# LPC2148_Engine_Room.net
KiCad netlist of a schematic drawn in EAGLE
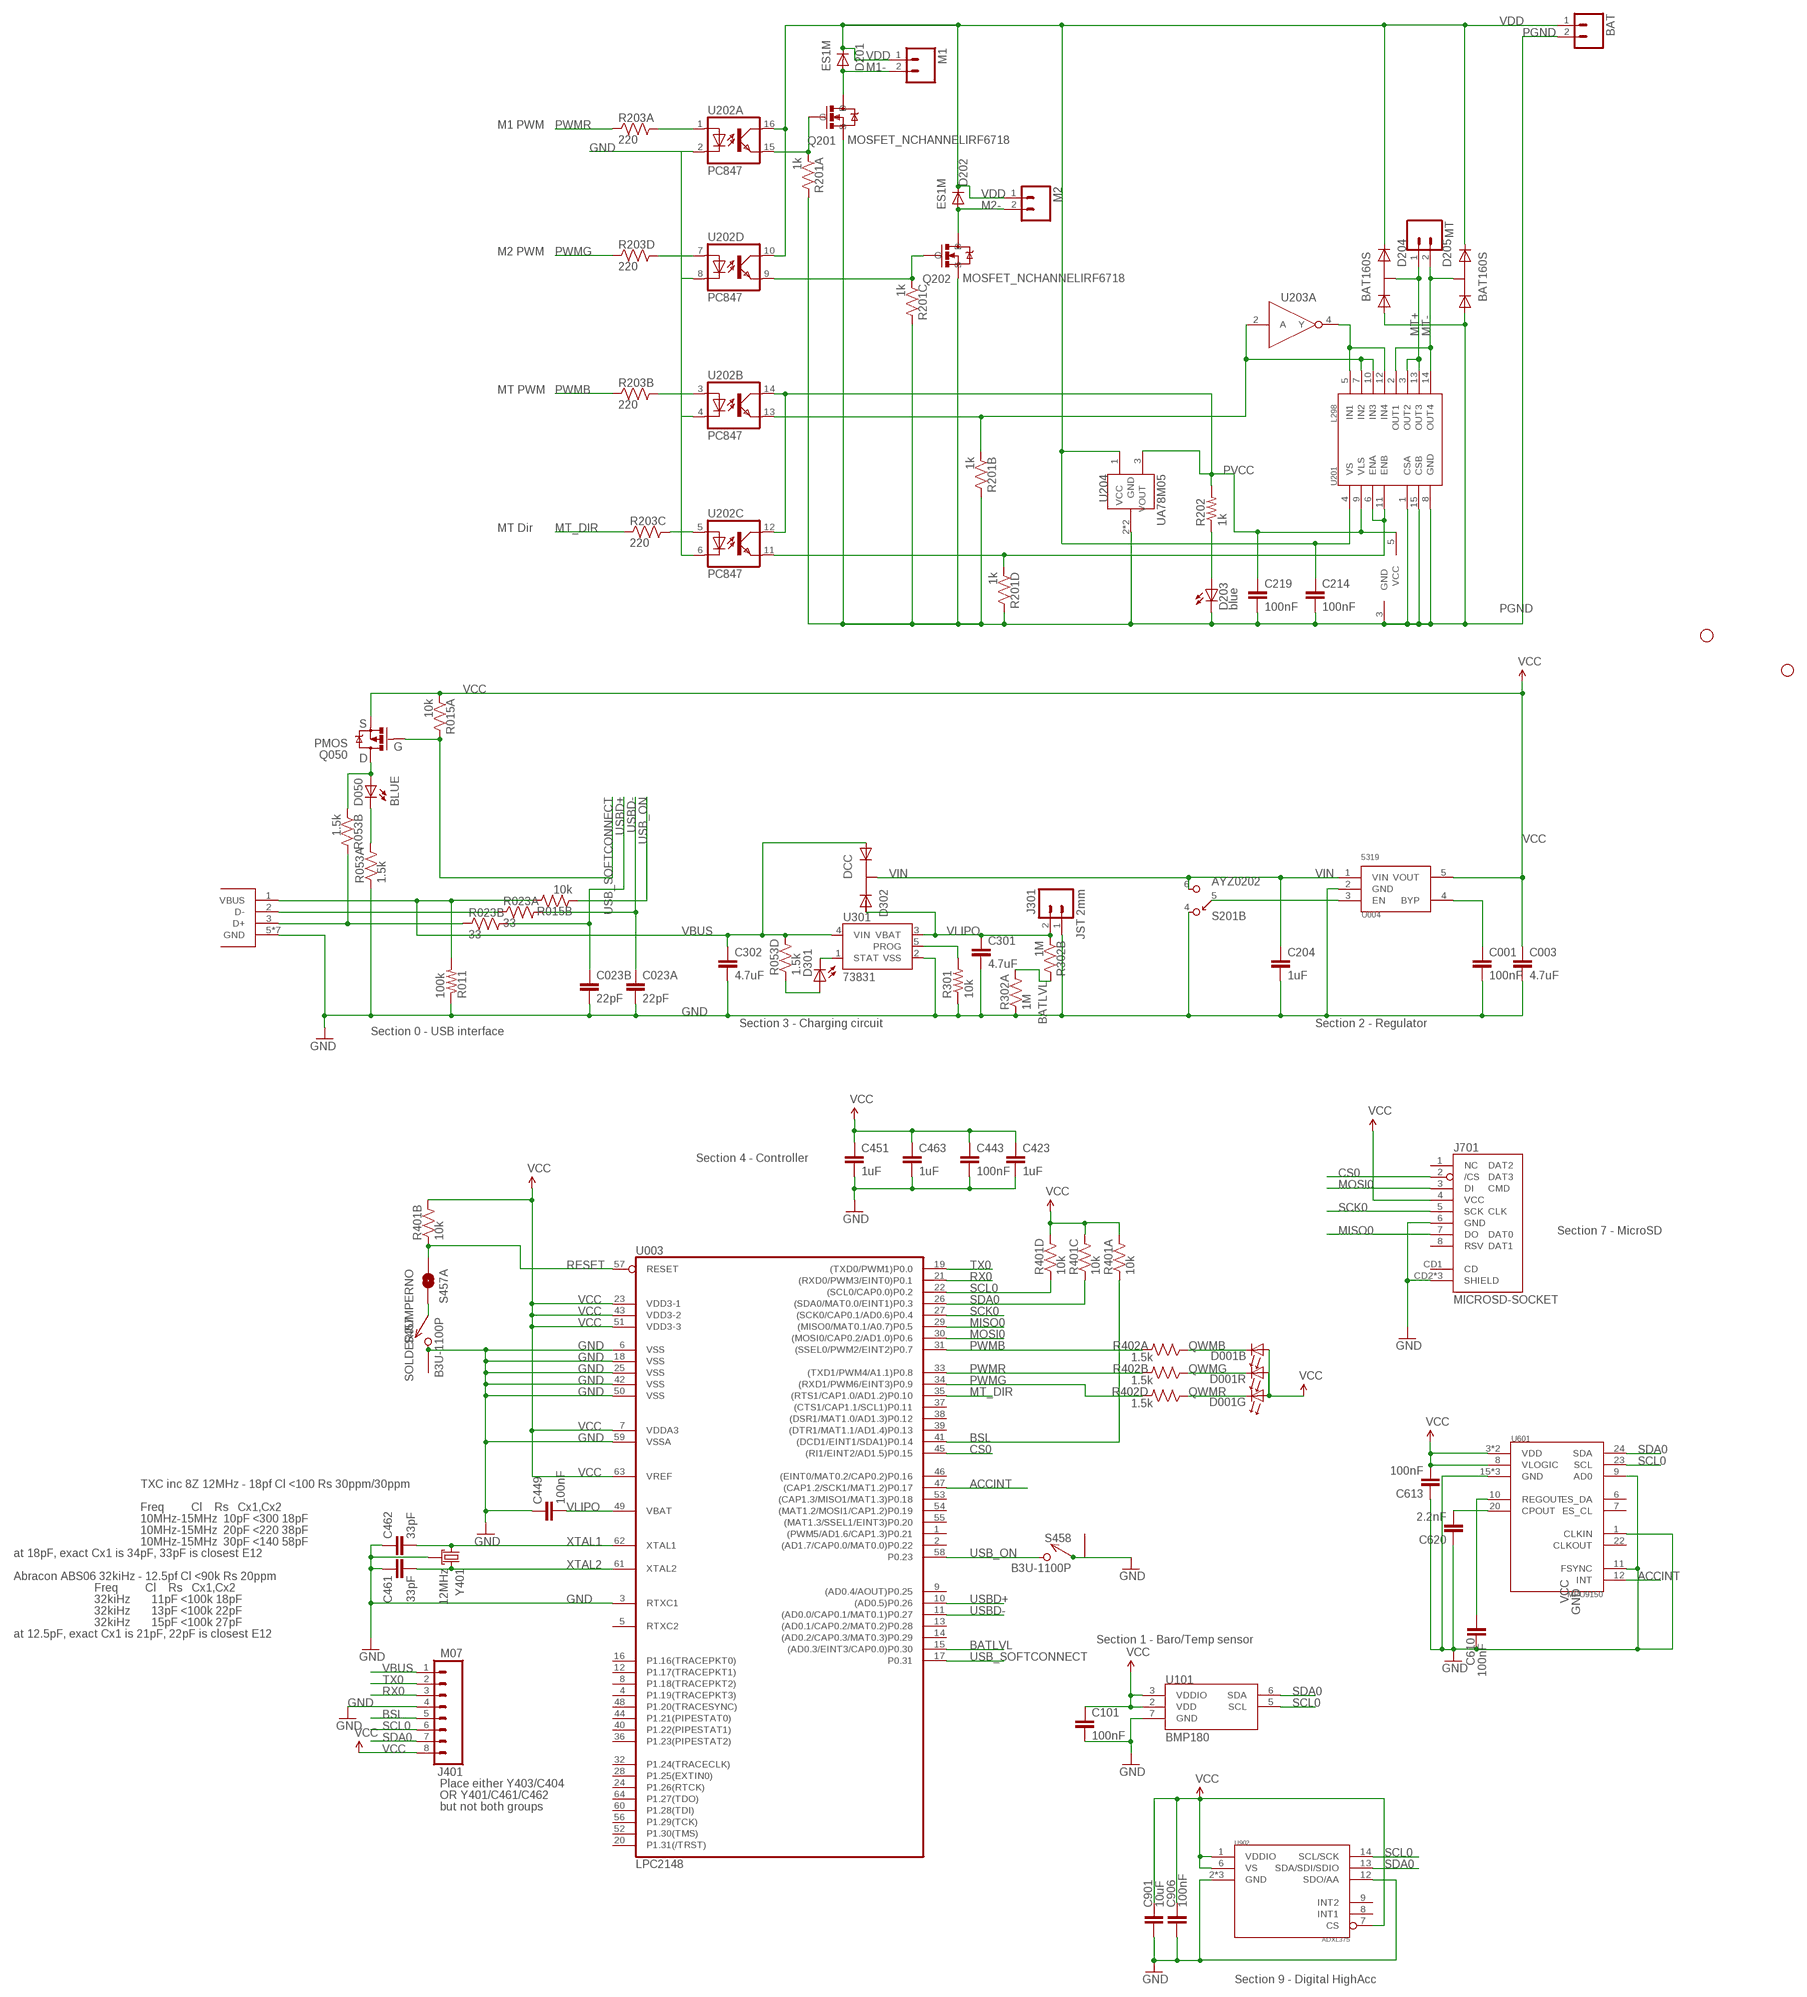
[diagram p0: schematic, sheet 1]

(export (version "E")
  (design (tool "Eeschema 10.0.6"))
  (components
    (comp (ref "BAT")
      (value "M02PTH4")
      (footprint "eagle-import:1X02_XTRA_BIG")
      (libsource (lib "eagle-import") (part "M02PTH4"))
    )
    (comp (ref "C001")
      (value "100nF")
      (footprint "eagle-import:0402-CAP")
      (libsource (lib "eagle-import") (part "CAP0402-CAP"))
    )
    (comp (ref "C003")
      (value "4.7uF")
      (footprint "eagle-import:0402-CAP")
      (libsource (lib "eagle-import") (part "CAP0402-CAP"))
    )
    (comp (ref "C023")
      (value "22pF")
      (footprint "eagle-import:CKCM25")
      (fields (field (name "DIGIKEY") "445-1860-1-ND"))
      (libsource (lib "eagle-import") (part "CKCM25"))
    )
    (comp (ref "C101")
      (value "100nF")
      (footprint "eagle-import:0402-CAP")
      (libsource (lib "eagle-import") (part "CAP0402-CAP"))
    )
    (comp (ref "C204")
      (value "1uF")
      (footprint "eagle-import:0402-CAP")
      (libsource (lib "eagle-import") (part "CAP0402-CAP"))
    )
    (comp (ref "C214")
      (value "100nF")
      (footprint "eagle-import:0402-CAP")
      (libsource (lib "eagle-import") (part "CAP0402-CAP"))
    )
    (comp (ref "C219")
      (value "100nF")
      (footprint "eagle-import:0402-CAP")
      (libsource (lib "eagle-import") (part "CAP0402-CAP"))
    )
    (comp (ref "C301")
      (value "4.7uF")
      (footprint "eagle-import:0402-CAP")
      (libsource (lib "eagle-import") (part "CAP0402-CAP"))
    )
    (comp (ref "C302")
      (value "4.7uF")
      (footprint "eagle-import:0402-CAP")
      (libsource (lib "eagle-import") (part "CAP0402-CAP"))
    )
    (comp (ref "C423")
      (value "1uF")
      (footprint "eagle-import:0402-CAP")
      (libsource (lib "eagle-import") (part "CAP0402-CAP"))
    )
    (comp (ref "C443")
      (value "100nF")
      (footprint "eagle-import:0402-CAP")
      (libsource (lib "eagle-import") (part "CAP0402-CAP"))
    )
    (comp (ref "C449")
      (value "100nF")
      (footprint "eagle-import:0402-CAP")
      (libsource (lib "eagle-import") (part "CAP0402-CAP"))
    )
    (comp (ref "C451")
      (value "1uF")
      (footprint "eagle-import:0402-CAP")
      (libsource (lib "eagle-import") (part "CAP0402-CAP"))
    )
    (comp (ref "C461")
      (value "33pF")
      (footprint "eagle-import:0402-CAP")
      (libsource (lib "eagle-import") (part "CAP0402-CAP"))
    )
    (comp (ref "C462")
      (value "33pF")
      (footprint "eagle-import:0402-CAP")
      (libsource (lib "eagle-import") (part "CAP0402-CAP"))
    )
    (comp (ref "C463")
      (value "1uF")
      (footprint "eagle-import:0402-CAP")
      (libsource (lib "eagle-import") (part "CAP0402-CAP"))
    )
    (comp (ref "C610")
      (value "100nF")
      (footprint "eagle-import:0402-CAP")
      (libsource (lib "eagle-import") (part "CAP0402-CAP"))
    )
    (comp (ref "C613")
      (value "100nF")
      (footprint "eagle-import:0402-CAP")
      (libsource (lib "eagle-import") (part "CAP0402-CAP"))
    )
    (comp (ref "C620")
      (value "2.2nF")
      (footprint "eagle-import:0402-CAP")
      (libsource (lib "eagle-import") (part "CAP0402-CAP"))
    )
    (comp (ref "C901")
      (value "10uF")
      (footprint "eagle-import:0603-CAP")
      (libsource (lib "eagle-import") (part "CAP0603-CAP"))
    )
    (comp (ref "C906")
      (value "100nF")
      (footprint "eagle-import:0402-CAP")
      (libsource (lib "eagle-import") (part "SparkFun-Passives_CAP0402-CAP"))
    )
    (comp (ref "D001")
      (value "SMLP36RGB2W(R)")
      (footprint "eagle-import:SMLP36")
      (fields (field (name "DIGIKEY") "846-1097-1-ND"))
      (libsource (lib "eagle-import") (part "SMLP36RGB2W(R)"))
    )
    (comp (ref "D050")
      (value "BLUE")
      (footprint "eagle-import:LED-0603")
      (libsource (lib "eagle-import") (part "LED0603"))
    )
    (comp (ref "D201")
      (value "ES1M")
      (footprint "eagle-import:DO-214AC")
      (libsource (lib "eagle-import") (part "DIODE-DO-214AC"))
    )
    (comp (ref "D202")
      (value "ES1M")
      (footprint "eagle-import:DO-214AC")
      (libsource (lib "eagle-import") (part "DIODE-DO-214AC"))
    )
    (comp (ref "D203")
      (value "blue")
      (footprint "eagle-import:LED-0603")
      (libsource (lib "eagle-import") (part "LED0603"))
    )
    (comp (ref "D204")
      (value "BAT160S")
      (footprint "eagle-import:SOT-223")
      (libsource (lib "eagle-import") (part "BAT160S"))
    )
    (comp (ref "D205")
      (value "BAT160S")
      (footprint "eagle-import:SOT-223")
      (libsource (lib "eagle-import") (part "BAT160S"))
    )
    (comp (ref "D301")
      (value "YELLOW")
      (footprint "eagle-import:LED-0603")
      (libsource (lib "eagle-import") (part "LED0603"))
    )
    (comp (ref "D302")
      (value "DCC")
      (footprint "eagle-import:SOT-23-3")
      (libsource (lib "eagle-import") (part "PMEG2005CT"))
    )
    (comp (ref "J004")
      (value "USB_MICROB_JSTGCT")
      (footprint "eagle-import:USB_MICROB_3075")
      (libsource (lib "eagle-import") (part "USB_MICROB_JSTGCT"))
    )
    (comp (ref "J301")
      (value "JST 2mm")
      (footprint "eagle-import:JST-2-SMD")
      (libsource (lib "eagle-import") (part "M02-JST-2MM-SMT"))
    )
    (comp (ref "J401")
      (value "M07")
      (footprint "eagle-import:1X08")
      (libsource (lib "eagle-import") (part "M081X08"))
    )
    (comp (ref "J701")
      (value "MICROSD-SOCKET")
      (footprint "eagle-import:MICROSD-SOCKET-PP")
      (libsource (lib "eagle-import") (part "MICROSD-SOCKET"))
    )
    (comp (ref "JP1")
      (value "STAND-OFF")
      (footprint "eagle-import:STAND-OFF")
      (libsource (lib "eagle-import") (part "STAND-OFF"))
    )
    (comp (ref "JP2")
      (value "STAND-OFF")
      (footprint "eagle-import:STAND-OFF")
      (libsource (lib "eagle-import") (part "STAND-OFF"))
    )
    (comp (ref "M1")
      (value "M02PTH4")
      (footprint "eagle-import:1X02_XTRA_BIG")
      (libsource (lib "eagle-import") (part "M02PTH4"))
    )
    (comp (ref "M2")
      (value "M02PTH4")
      (footprint "eagle-import:1X02_XTRA_BIG")
      (libsource (lib "eagle-import") (part "M02PTH4"))
    )
    (comp (ref "MT")
      (value "M02PTH")
      (footprint "eagle-import:1X02")
      (libsource (lib "eagle-import") (part "M02PTH"))
    )
    (comp (ref "Q050")
      (value "PMOS")
      (footprint "eagle-import:SOT23-3")
      (libsource (lib "eagle-import") (part "MOSFET-PCHANNELSMD"))
    )
    (comp (ref "Q201")
      (value "MOSFET_NCHANNELIRF6718")
      (footprint "eagle-import:DIRECTFET_L6")
      (libsource (lib "eagle-import") (part "MOSFET_NCHANNELIRF6718"))
    )
    (comp (ref "Q202")
      (value "MOSFET_NCHANNELIRF6718")
      (footprint "eagle-import:DIRECTFET_L6")
      (libsource (lib "eagle-import") (part "MOSFET_NCHANNELIRF6718"))
    )
    (comp (ref "R011")
      (value "100k")
      (footprint "eagle-import:0402-RES")
      (libsource (lib "eagle-import") (part "RESISTOR0402-RES"))
    )
    (comp (ref "R015")
      (value "10k")
      (footprint "eagle-import:CRA02")
      (fields (field (name "DIGIKEY") "Y5103CT-ND"))
      (libsource (lib "eagle-import") (part "RP2EXB24V"))
    )
    (comp (ref "R023")
      (value "33")
      (footprint "eagle-import:CRA02")
      (libsource (lib "eagle-import") (part "RP2EXB24V"))
    )
    (comp (ref "R053")
      (value "1.5k")
      (footprint "eagle-import:CRA04")
      (fields (field (name "DIGIKEY") "CRA4S81.5KCT-ND"))
      (libsource (lib "eagle-import") (part "RP404"))
    )
    (comp (ref "R201")
      (value "1k")
      (footprint "eagle-import:CRA04")
      (libsource (lib "eagle-import") (part "RP404"))
    )
    (comp (ref "R202")
      (value "1k")
      (footprint "eagle-import:0402-RES")
      (libsource (lib "eagle-import") (part "RESISTOR0402-RES"))
    )
    (comp (ref "R203")
      (value "220")
      (footprint "eagle-import:CRA04")
      (libsource (lib "eagle-import") (part "RP404"))
    )
    (comp (ref "R301")
      (value "10k")
      (footprint "eagle-import:0402-RES")
      (libsource (lib "eagle-import") (part "RESISTOR0402-RES"))
    )
    (comp (ref "R302")
      (value "1M")
      (footprint "eagle-import:CRA02")
      (libsource (lib "eagle-import") (part "RP2EXB24V"))
    )
    (comp (ref "R401")
      (value "10k")
      (footprint "eagle-import:CRA04")
      (fields (field (name "DIGIKEY") "CRA4S810KCT-ND"))
      (libsource (lib "eagle-import") (part "RP404"))
    )
    (comp (ref "R402")
      (value "1.5k")
      (footprint "eagle-import:CRA04")
      (fields (field (name "DIGIKEY") "CRA4S81.5KCT-ND"))
      (libsource (lib "eagle-import") (part "RP404"))
    )
    (comp (ref "S201")
      (value "AYZ0202")
      (footprint "eagle-import:AYZ0202")
      (libsource (lib "eagle-import") (part "AYZ0202"))
    )
    (comp (ref "S457")
      (value "B3U-1100P")
      (footprint "eagle-import:B3U-1100P")
      (fields (field (name "DIGIKEY") "SW1021CT-ND"))
      (libsource (lib "eagle-import") (part "B3U-1100P"))
    )
    (comp (ref "S457A")
      (value "SOLDERJUMPERNO")
      (footprint "eagle-import:SJ_2S-NO")
      (libsource (lib "eagle-import") (part "SOLDERJUMPERNO"))
    )
    (comp (ref "S458")
      (value "B3U-1100P")
      (footprint "eagle-import:B3U-1100P")
      (fields (field (name "DIGIKEY") "SW1021CT-ND"))
      (libsource (lib "eagle-import") (part "B3U-1100P"))
    )
    (comp (ref "U003")
      (value "LPC2148")
      (footprint "eagle-import:SQFP-S-10X10-64")
      (libsource (lib "eagle-import") (part "LPC213X"))
    )
    (comp (ref "U004")
      (value "5319")
      (footprint "eagle-import:SOT-23-5")
      (libsource (lib "eagle-import") (part "MIC5319D5"))
    )
    (comp (ref "U101")
      (value "BMP180")
      (footprint "eagle-import:BMP180")
      (libsource (lib "eagle-import") (part "BMP180"))
    )
    (comp (ref "U201")
      (value "L298")
      (footprint "eagle-import:MULTIWATT15")
      (libsource (lib "eagle-import") (part "L298"))
    )
    (comp (ref "U202")
      (value "PC847")
      (footprint "eagle-import:DIL16")
      (libsource (lib "eagle-import") (part "PC847"))
    )
    (comp (ref "U203")
      (value "MC74VHC1G04")
      (footprint "eagle-import:SOT-23-5")
      (libsource (lib "eagle-import") (part "MC74VHC1G04"))
    )
    (comp (ref "U204")
      (value "UA78M05")
      (footprint "eagle-import:SOT-223")
      (libsource (lib "eagle-import") (part "UA78M05"))
    )
    (comp (ref "U301")
      (value "73831")
      (footprint "eagle-import:SOT23-5")
      (libsource (lib "eagle-import") (part "MCP73831"))
    )
    (comp (ref "U601")
      (value "MPU9150")
      (footprint "eagle-import:LLGA24")
      (libsource (lib "eagle-import") (part "MPU9150"))
    )
    (comp (ref "U902")
      (value "ADXL375")
      (footprint "eagle-import:ADXL375")
      (libsource (lib "eagle-import") (part "ADXL375"))
    )
    (comp (ref "Y401")
      (value "12MHz")
      (footprint "eagle-import:CRYSTAL_SMD_2MM_2_5MM")
      (libsource (lib "eagle-import") (part "CX2520"))
    )
  )
  (nets
    (net (code "1") (name "/ACCINT") (class "Default")
      (node (ref "U003") (pin "47") (pinfunction "(CAP1.2/SCK1/MAT1.2)P0.17_47") (pintype "bidirectional"))
      (node (ref "U601") (pin "12") (pinfunction "INT_12") (pintype "bidirectional"))
    )
    (net (code "2") (name "/BATLVL") (class "Default")
      (node (ref "R302") (pin "3") (pinfunction "2_3") (pintype "passive"))
      (node (ref "R302") (pin "4") (pinfunction "2_4") (pintype "passive"))
      (node (ref "U003") (pin "15") (pinfunction "(AD0.3/EINT3/CAP0.0)P0.30_15") (pintype "bidirectional"))
    )
    (net (code "3") (name "/BSL") (class "Default")
      (node (ref "J401") (pin "5") (pinfunction "5_5") (pintype "passive"))
      (node (ref "R401") (pin "1") (pinfunction "1_1") (pintype "passive"))
      (node (ref "U003") (pin "41") (pinfunction "(DCD1/EINT1/SDA1)P0.14_41") (pintype "bidirectional"))
    )
    (net (code "4") (name "/CS0") (class "Default")
      (node (ref "J701") (pin "2") (pinfunction "/CS_2") (pintype "bidirectional"))
      (node (ref "U003") (pin "45") (pinfunction "(RI1/EINT2/AD1.5)P0.15_45") (pintype "bidirectional"))
    )
    (net (code "5") (name "/M1-") (class "Default")
      (node (ref "D201") (pin "A") (pinfunction "A_A") (pintype "passive"))
      (node (ref "M1") (pin "2") (pinfunction "2_2") (pintype "passive"))
      (node (ref "Q201") (pin "D1") (pinfunction "D_D1") (pintype "passive"))
      (node (ref "Q201") (pin "D2") (pinfunction "D_D2") (pintype "passive"))
    )
    (net (code "6") (name "/M2-") (class "Default")
      (node (ref "D202") (pin "A") (pinfunction "A_A") (pintype "passive"))
      (node (ref "M2") (pin "2") (pinfunction "2_2") (pintype "passive"))
      (node (ref "Q202") (pin "D1") (pinfunction "D_D1") (pintype "passive"))
      (node (ref "Q202") (pin "D2") (pinfunction "D_D2") (pintype "passive"))
    )
    (net (code "7") (name "/MISO0") (class "Default")
      (node (ref "J701") (pin "7") (pinfunction "DO_7") (pintype "bidirectional"))
      (node (ref "U003") (pin "29") (pinfunction "(MISO0/MAT0.1/A0.7)P0.5_29") (pintype "bidirectional"))
    )
    (net (code "8") (name "/MOSI0") (class "Default")
      (node (ref "J701") (pin "3") (pinfunction "DI_3") (pintype "bidirectional"))
      (node (ref "U003") (pin "30") (pinfunction "(MOSI0/CAP0.2/AD1.0)P0.6_30") (pintype "bidirectional"))
    )
    (net (code "9") (name "/MT+") (class "Default")
      (node (ref "D204") (pin "4") (pinfunction "K1A2_4") (pintype "passive"))
      (node (ref "MT") (pin "1") (pinfunction "1_1") (pintype "passive"))
      (node (ref "U201") (pin "13") (pinfunction "OUT3_13") (pintype "bidirectional"))
      (node (ref "U201") (pin "3") (pinfunction "OUT2_3") (pintype "bidirectional"))
    )
    (net (code "10") (name "/MT-") (class "Default")
      (node (ref "D205") (pin "4") (pinfunction "K1A2_4") (pintype "passive"))
      (node (ref "MT") (pin "2") (pinfunction "2_2") (pintype "passive"))
      (node (ref "U201") (pin "14") (pinfunction "OUT4_14") (pintype "bidirectional"))
      (node (ref "U201") (pin "2") (pinfunction "OUT1_2") (pintype "bidirectional"))
    )
    (net (code "11") (name "/MT_DIR") (class "Default")
      (node (ref "R203") (pin "3") (pinfunction "1_3") (pintype "passive"))
      (node (ref "U003") (pin "35") (pinfunction "(RTS1/CAP1.0/AD1.2)P0.10_35") (pintype "bidirectional"))
    )
    (net (code "12") (name "/PGND") (class "Default")
      (node (ref "BAT") (pin "2") (pinfunction "2_2") (pintype "passive"))
      (node (ref "C214") (pin "2") (pinfunction "2_2") (pintype "passive"))
      (node (ref "C219") (pin "2") (pinfunction "2_2") (pintype "passive"))
      (node (ref "D203") (pin "C") (pinfunction "C_C") (pintype "passive"))
      (node (ref "D204") (pin "1") (pinfunction "A1_1") (pintype "passive"))
      (node (ref "D205") (pin "1") (pinfunction "A1_1") (pintype "passive"))
      (node (ref "Q201") (pin "S") (pinfunction "S_S") (pintype "passive"))
      (node (ref "Q202") (pin "S") (pinfunction "S_S") (pintype "passive"))
      (node (ref "R201") (pin "5") (pinfunction "2_5") (pintype "passive"))
      (node (ref "R201") (pin "6") (pinfunction "2_6") (pintype "passive"))
      (node (ref "R201") (pin "7") (pinfunction "2_7") (pintype "passive"))
      (node (ref "R201") (pin "8") (pinfunction "2_8") (pintype "passive"))
      (node (ref "U201") (pin "1") (pinfunction "CSA_1") (pintype "bidirectional"))
      (node (ref "U201") (pin "15") (pinfunction "CSB_15") (pintype "bidirectional"))
      (node (ref "U201") (pin "8") (pinfunction "GND_8") (pintype "bidirectional"))
      (node (ref "U203") (pin "3") (pinfunction "GND_3") (pintype "bidirectional"))
      (node (ref "U204") (pin "2") (pinfunction "GND_2") (pintype "bidirectional"))
      (node (ref "U204") (pin "4") (pinfunction "GND_4") (pintype "bidirectional"))
    )
    (net (code "13") (name "/PVCC") (class "Default")
      (node (ref "C219") (pin "1") (pinfunction "1_1") (pintype "passive"))
      (node (ref "R202") (pin "2") (pinfunction "2_2") (pintype "passive"))
      (node (ref "U201") (pin "9") (pinfunction "VLS_9") (pintype "bidirectional"))
      (node (ref "U202") (pin "12") (pinfunction "COL_12") (pintype "passive"))
      (node (ref "U202") (pin "14") (pinfunction "COL_14") (pintype "passive"))
      (node (ref "U203") (pin "5") (pinfunction "VCC_5") (pintype "bidirectional"))
      (node (ref "U204") (pin "3") (pinfunction "VOUT_3") (pintype "bidirectional"))
    )
    (net (code "14") (name "/PWMB") (class "Default")
      (node (ref "R203") (pin "2") (pinfunction "1_2") (pintype "passive"))
      (node (ref "R402") (pin "8") (pinfunction "2_8") (pintype "passive"))
      (node (ref "U003") (pin "31") (pinfunction "(SSEL0/PWM2/EINT2)P0.7_31") (pintype "bidirectional"))
    )
    (net (code "15") (name "/PWMG") (class "Default")
      (node (ref "R203") (pin "4") (pinfunction "1_4") (pintype "passive"))
      (node (ref "R402") (pin "5") (pinfunction "2_5") (pintype "passive"))
      (node (ref "U003") (pin "34") (pinfunction "(RXD1/PWM6/EINT3)P0.9_34") (pintype "bidirectional"))
    )
    (net (code "16") (name "/PWMR") (class "Default")
      (node (ref "R203") (pin "1") (pinfunction "1_1") (pintype "passive"))
      (node (ref "R402") (pin "7") (pinfunction "2_7") (pintype "passive"))
      (node (ref "U003") (pin "33") (pinfunction "(TXD1/PWM4/A1.1)P0.8_33") (pintype "bidirectional"))
    )
    (net (code "17") (name "/QWMB") (class "Default")
      (node (ref "D001") (pin "1") (pinfunction "C_1") (pintype "passive"))
      (node (ref "R402") (pin "1") (pinfunction "1_1") (pintype "passive"))
    )
    (net (code "18") (name "/QWMG") (class "Default")
      (node (ref "D001") (pin "5") (pinfunction "C_5") (pintype "passive"))
      (node (ref "R402") (pin "4") (pinfunction "1_4") (pintype "passive"))
    )
    (net (code "19") (name "/QWMR") (class "Default")
      (node (ref "D001") (pin "3") (pinfunction "C_3") (pintype "passive"))
      (node (ref "R402") (pin "2") (pinfunction "1_2") (pintype "passive"))
    )
    (net (code "20") (name "/RESET") (class "Default")
      (node (ref "R401") (pin "2") (pinfunction "1_2") (pintype "passive"))
      (node (ref "S457A") (pin "1") (pinfunction "1_1") (pintype "passive"))
      (node (ref "U003") (pin "57") (pinfunction "RESET_57") (pintype "input"))
    )
    (net (code "21") (name "/RX0") (class "Default")
      (node (ref "J401") (pin "3") (pinfunction "3_3") (pintype "passive"))
      (node (ref "U003") (pin "21") (pinfunction "(RXD0/PWM3/EINT0)P0.1_21") (pintype "bidirectional"))
    )
    (net (code "22") (name "/SCK0") (class "Default")
      (node (ref "J701") (pin "5") (pinfunction "SCK_5") (pintype "bidirectional"))
      (node (ref "U003") (pin "27") (pinfunction "(SCK0/CAP0.1/AD0.6)P0.4_27") (pintype "bidirectional"))
    )
    (net (code "23") (name "/SCL0") (class "Default")
      (node (ref "J401") (pin "6") (pinfunction "6_6") (pintype "passive"))
      (node (ref "R401") (pin "4") (pinfunction "1_4") (pintype "passive"))
      (node (ref "U003") (pin "22") (pinfunction "(SCL0/CAP0.0)P0.2_22") (pintype "bidirectional"))
      (node (ref "U101") (pin "5") (pinfunction "SCL_5") (pintype "input"))
      (node (ref "U601") (pin "23") (pinfunction "SCL_23") (pintype "bidirectional"))
      (node (ref "U902") (pin "14") (pinfunction "SCL/SCK_14") (pintype "input"))
    )
    (net (code "24") (name "/SDA0") (class "Default")
      (node (ref "J401") (pin "7") (pinfunction "7_7") (pintype "passive"))
      (node (ref "R401") (pin "3") (pinfunction "1_3") (pintype "passive"))
      (node (ref "U003") (pin "26") (pinfunction "(SDA0/MAT0.0/EINT1)P0.3_26") (pintype "bidirectional"))
      (node (ref "U101") (pin "6") (pinfunction "SDA_6") (pintype "bidirectional"))
      (node (ref "U601") (pin "24") (pinfunction "SDA_24") (pintype "bidirectional"))
      (node (ref "U902") (pin "13") (pinfunction "SDA/SDI/SDIO_13") (pintype "bidirectional"))
    )
    (net (code "25") (name "/TX0") (class "Default")
      (node (ref "J401") (pin "2") (pinfunction "2_2") (pintype "passive"))
      (node (ref "U003") (pin "19") (pinfunction "(TXD0/PWM1)P0.0_19") (pintype "bidirectional"))
    )
    (net (code "26") (name "/USBD+") (class "Default")
      (node (ref "C023") (pin "2") (pinfunction "1_2") (pintype "passive"))
      (node (ref "R023") (pin "3") (pinfunction "2_3") (pintype "passive"))
      (node (ref "U003") (pin "10") (pinfunction "(AD0.5)P0.26_10") (pintype "bidirectional"))
    )
    (net (code "27") (name "/USBD-") (class "Default")
      (node (ref "C023") (pin "1") (pinfunction "1_1") (pintype "passive"))
      (node (ref "R023") (pin "4") (pinfunction "2_4") (pintype "passive"))
      (node (ref "U003") (pin "11") (pinfunction "(AD0.0/CAP0.1/MAT0.1)P0.27_11") (pintype "bidirectional"))
    )
    (net (code "28") (name "/USB_ON") (class "Default")
      (node (ref "R015") (pin "2") (pinfunction "1_2") (pintype "passive"))
      (node (ref "S458") (pin "P$2") (pinfunction "2_P$2") (pintype "bidirectional"))
      (node (ref "U003") (pin "58") (pinfunction "P0.23_58") (pintype "bidirectional"))
    )
    (net (code "29") (name "/USB_SOFTCONNECT") (class "Default")
      (node (ref "Q050") (pin "1") (pinfunction "G_1") (pintype "passive"))
      (node (ref "R015") (pin "4") (pinfunction "2_4") (pintype "passive"))
      (node (ref "U003") (pin "17") (pinfunction "P0.31_17") (pintype "output"))
    )
    (net (code "30") (name "/VBUS") (class "Default")
      (node (ref "C302") (pin "1") (pinfunction "1_1") (pintype "passive"))
      (node (ref "D302") (pin "1") (pinfunction "A1_1") (pintype "passive"))
      (node (ref "J004") (pin "1") (pinfunction "VBUS_1") (pintype "bidirectional"))
      (node (ref "J401") (pin "1") (pinfunction "1_1") (pintype "passive"))
      (node (ref "R011") (pin "2") (pinfunction "2_2") (pintype "passive"))
      (node (ref "R015") (pin "3") (pinfunction "2_3") (pintype "passive"))
      (node (ref "R053") (pin "5") (pinfunction "2_5") (pintype "passive"))
      (node (ref "U301") (pin "4") (pinfunction "VIN_4") (pintype "power_in"))
    )
    (net (code "31") (name "/VDD") (class "Default")
      (node (ref "BAT") (pin "1") (pinfunction "1_1") (pintype "passive"))
      (node (ref "C214") (pin "1") (pinfunction "1_1") (pintype "passive"))
      (node (ref "D201") (pin "C") (pinfunction "C_C") (pintype "passive"))
      (node (ref "D202") (pin "C") (pinfunction "C_C") (pintype "passive"))
      (node (ref "D204") (pin "3") (pinfunction "K2_3") (pintype "passive"))
      (node (ref "D205") (pin "3") (pinfunction "K2_3") (pintype "passive"))
      (node (ref "M1") (pin "1") (pinfunction "1_1") (pintype "passive"))
      (node (ref "M2") (pin "1") (pinfunction "1_1") (pintype "passive"))
      (node (ref "U201") (pin "4") (pinfunction "VS_4") (pintype "bidirectional"))
      (node (ref "U202") (pin "10") (pinfunction "COL_10") (pintype "passive"))
      (node (ref "U202") (pin "16") (pinfunction "COL_16") (pintype "passive"))
      (node (ref "U204") (pin "1") (pinfunction "VCC_1") (pintype "bidirectional"))
    )
    (net (code "32") (name "/VIN") (class "Default")
      (node (ref "C204") (pin "1") (pinfunction "1_1") (pintype "passive"))
      (node (ref "D302") (pin "3") (pinfunction "K_3") (pintype "passive"))
      (node (ref "S201") (pin "6") (pinfunction "P$2_6") (pintype "bidirectional"))
      (node (ref "U004") (pin "1") (pinfunction "VIN_1") (pintype "bidirectional"))
    )
    (net (code "33") (name "/VLIPO") (class "Default")
      (node (ref "C301") (pin "1") (pinfunction "1_1") (pintype "passive"))
      (node (ref "C449") (pin "2") (pinfunction "2_2") (pintype "passive"))
      (node (ref "D302") (pin "2") (pinfunction "A2_2") (pintype "passive"))
      (node (ref "J301") (pin "2") (pinfunction "2_2") (pintype "passive"))
      (node (ref "R302") (pin "2") (pinfunction "1_2") (pintype "passive"))
      (node (ref "U003") (pin "49") (pinfunction "VBAT_49") (pintype "power_in"))
      (node (ref "U301") (pin "3") (pinfunction "VBAT_3") (pintype "power_in"))
    )
    (net (code "34") (name "/XTAL1") (class "Default")
      (node (ref "C462") (pin "2") (pinfunction "2_2") (pintype "passive"))
      (node (ref "U003") (pin "62") (pinfunction "XTAL1_62") (pintype "input"))
      (node (ref "Y401") (pin "1") (pinfunction "1_1") (pintype "passive"))
    )
    (net (code "35") (name "/XTAL2") (class "Default")
      (node (ref "C461") (pin "2") (pinfunction "2_2") (pintype "passive"))
      (node (ref "U003") (pin "61") (pinfunction "XTAL2_61") (pintype "output"))
      (node (ref "Y401") (pin "3") (pinfunction "2_3") (pintype "passive"))
    )
    (net (code "36") (name "GND") (class "Default")
      (node (ref "C001") (pin "2") (pinfunction "2_2") (pintype "passive"))
      (node (ref "C003") (pin "2") (pinfunction "2_2") (pintype "passive"))
      (node (ref "C023") (pin "3") (pinfunction "2_3") (pintype "passive"))
      (node (ref "C023") (pin "4") (pinfunction "2_4") (pintype "passive"))
      (node (ref "C101") (pin "2") (pinfunction "2_2") (pintype "passive"))
      (node (ref "C204") (pin "2") (pinfunction "2_2") (pintype "passive"))
      (node (ref "C301") (pin "2") (pinfunction "2_2") (pintype "passive"))
      (node (ref "C302") (pin "2") (pinfunction "2_2") (pintype "passive"))
      (node (ref "C423") (pin "2") (pinfunction "2_2") (pintype "passive"))
      (node (ref "C443") (pin "2") (pinfunction "2_2") (pintype "passive"))
      (node (ref "C449") (pin "1") (pinfunction "1_1") (pintype "passive"))
      (node (ref "C451") (pin "2") (pinfunction "2_2") (pintype "passive"))
      (node (ref "C461") (pin "1") (pinfunction "1_1") (pintype "passive"))
      (node (ref "C462") (pin "1") (pinfunction "1_1") (pintype "passive"))
      (node (ref "C463") (pin "2") (pinfunction "2_2") (pintype "passive"))
      (node (ref "C610") (pin "2") (pinfunction "2_2") (pintype "passive"))
      (node (ref "C613") (pin "1") (pinfunction "1_1") (pintype "passive"))
      (node (ref "C620") (pin "1") (pinfunction "1_1") (pintype "passive"))
      (node (ref "C901") (pin "2") (pinfunction "2_2") (pintype "passive"))
      (node (ref "C906") (pin "2") (pinfunction "2_2") (pintype "passive"))
      (node (ref "J004") (pin "5") (pinfunction "GND_5") (pintype "bidirectional"))
      (node (ref "J004") (pin "P$1") (pinfunction "GND_P$1") (pintype "bidirectional"))
      (node (ref "J004") (pin "P$10") (pinfunction "GND_P$10") (pintype "bidirectional"))
      (node (ref "J004") (pin "P$2") (pinfunction "GND_P$2") (pintype "bidirectional"))
      (node (ref "J004") (pin "P$3") (pinfunction "GND_P$3") (pintype "bidirectional"))
      (node (ref "J004") (pin "P$4") (pinfunction "GND_P$4") (pintype "bidirectional"))
      (node (ref "J004") (pin "P$8") (pinfunction "GND_P$8") (pintype "bidirectional"))
      (node (ref "J301") (pin "1") (pinfunction "1_1") (pintype "passive"))
      (node (ref "J401") (pin "4") (pinfunction "4_4") (pintype "passive"))
      (node (ref "J701") (pin "6") (pinfunction "GND_6") (pintype "bidirectional"))
      (node (ref "J701") (pin "CD2") (pinfunction "SHIELD_CD2") (pintype "bidirectional"))
      (node (ref "J701") (pin "GND1") (pinfunction "SHIELD_GND1") (pintype "bidirectional"))
      (node (ref "J701") (pin "GND3") (pinfunction "SHIELD_GND3") (pintype "bidirectional"))
      (node (ref "R011") (pin "1") (pinfunction "1_1") (pintype "passive"))
      (node (ref "R053") (pin "1") (pinfunction "1_1") (pintype "passive"))
      (node (ref "R301") (pin "1") (pinfunction "1_1") (pintype "passive"))
      (node (ref "R302") (pin "1") (pinfunction "1_1") (pintype "passive"))
      (node (ref "S201") (pin "4") (pinfunction "P$1_4") (pintype "bidirectional"))
      (node (ref "S457") (pin "P$2") (pinfunction "2_P$2") (pintype "bidirectional"))
      (node (ref "S457") (pin "P$3") (pinfunction "1_P$3") (pintype "bidirectional"))
      (node (ref "S458") (pin "P$1") (pinfunction "1_P$1") (pintype "bidirectional"))
      (node (ref "S458") (pin "P$3") (pinfunction "1_P$3") (pintype "bidirectional"))
      (node (ref "U003") (pin "18") (pinfunction "VSS_18") (pintype "power_in"))
      (node (ref "U003") (pin "25") (pinfunction "VSS_25") (pintype "power_in"))
      (node (ref "U003") (pin "3") (pinfunction "RTXC1_3") (pintype "input"))
      (node (ref "U003") (pin "42") (pinfunction "VSS_42") (pintype "power_in"))
      (node (ref "U003") (pin "50") (pinfunction "VSS_50") (pintype "power_in"))
      (node (ref "U003") (pin "59") (pinfunction "VSSA_59") (pintype "power_in"))
      (node (ref "U003") (pin "6") (pinfunction "VSS_6") (pintype "power_in"))
      (node (ref "U004") (pin "2") (pinfunction "GND_2") (pintype "bidirectional"))
      (node (ref "U101") (pin "7") (pinfunction "GND_7") (pintype "power_in"))
      (node (ref "U202") (pin "2") (pinfunction "C_2") (pintype "passive"))
      (node (ref "U202") (pin "4") (pinfunction "C_4") (pintype "passive"))
      (node (ref "U202") (pin "6") (pinfunction "C_6") (pintype "passive"))
      (node (ref "U202") (pin "8") (pinfunction "C_8") (pintype "passive"))
      (node (ref "U301") (pin "2") (pinfunction "VSS_2") (pintype "power_in"))
      (node (ref "U601") (pin "1") (pinfunction "CLKIN_1") (pintype "bidirectional"))
      (node (ref "U601") (pin "11") (pinfunction "FSYNC_11") (pintype "bidirectional"))
      (node (ref "U601") (pin "15") (pinfunction "GND_15") (pintype "bidirectional"))
      (node (ref "U601") (pin "17") (pinfunction "GND_17") (pintype "bidirectional"))
      (node (ref "U601") (pin "18") (pinfunction "GND_18") (pintype "bidirectional"))
      (node (ref "U601") (pin "9") (pinfunction "AD0_9") (pintype "bidirectional"))
      (node (ref "U902") (pin "12") (pinfunction "SDO/AA_12") (pintype "bidirectional"))
      (node (ref "U902") (pin "2") (pinfunction "GND_2") (pintype "power_in"))
      (node (ref "U902") (pin "4") (pinfunction "GND_4") (pintype "power_in"))
      (node (ref "U902") (pin "5") (pinfunction "GND_5") (pintype "power_in"))
      (node (ref "Y401") (pin "2") (pinfunction "GND_2") (pintype "passive"))
      (node (ref "Y401") (pin "4") (pinfunction "GND_4") (pintype "passive"))
    )
    (net (code "37") (name "Net-(D203-PadA)") (class "Default")
      (node (ref "D203") (pin "A") (pinfunction "A_A") (pintype "passive"))
      (node (ref "R202") (pin "1") (pinfunction "1_1") (pintype "passive"))
    )
    (net (code "38") (name "Net-(J004-D+)") (class "Default")
      (node (ref "J004") (pin "3") (pinfunction "D+_3") (pintype "bidirectional"))
      (node (ref "R023") (pin "2") (pinfunction "1_2") (pintype "passive"))
      (node (ref "R053") (pin "7") (pinfunction "2_7") (pintype "passive"))
    )
    (net (code "39") (name "Net-(J004-D-)") (class "Default")
      (node (ref "J004") (pin "2") (pinfunction "D-_2") (pintype "bidirectional"))
      (node (ref "R023") (pin "1") (pinfunction "1_1") (pintype "passive"))
    )
    (net (code "40") (name "Net-(Q050-D)") (class "Default")
      (node (ref "D050") (pin "A") (pinfunction "A_A") (pintype "passive"))
      (node (ref "Q050") (pin "3") (pinfunction "D_3") (pintype "passive"))
      (node (ref "R053") (pin "2") (pinfunction "1_2") (pintype "passive"))
    )
    (net (code "41") (name "Net-(R053A-2)") (class "Default")
      (node (ref "D050") (pin "C") (pinfunction "C_C") (pintype "passive"))
      (node (ref "R053") (pin "8") (pinfunction "2_8") (pintype "passive"))
    )
    (net (code "42") (name "Net-(R053D-1)") (class "Default")
      (node (ref "D301") (pin "A") (pinfunction "A_A") (pintype "passive"))
      (node (ref "R053") (pin "4") (pinfunction "1_4") (pintype "passive"))
    )
    (net (code "43") (name "Net-(R201B-1)") (class "Default")
      (node (ref "R201") (pin "2") (pinfunction "1_2") (pintype "passive"))
      (node (ref "U201") (pin "10") (pinfunction "IN3_10") (pintype "bidirectional"))
      (node (ref "U201") (pin "7") (pinfunction "IN2_7") (pintype "bidirectional"))
      (node (ref "U202") (pin "13") (pinfunction "EMIT_13") (pintype "passive"))
      (node (ref "U203") (pin "2") (pinfunction "A_2") (pintype "input"))
    )
    (net (code "44") (name "Net-(R201C-1)") (class "Default")
      (node (ref "Q202") (pin "G") (pinfunction "G_G") (pintype "passive"))
      (node (ref "R201") (pin "3") (pinfunction "1_3") (pintype "passive"))
      (node (ref "U202") (pin "9") (pinfunction "EMIT_9") (pintype "passive"))
    )
    (net (code "45") (name "Net-(R201D-1)") (class "Default")
      (node (ref "R201") (pin "4") (pinfunction "1_4") (pintype "passive"))
      (node (ref "U201") (pin "11") (pinfunction "ENB_11") (pintype "bidirectional"))
      (node (ref "U201") (pin "6") (pinfunction "ENA_6") (pintype "bidirectional"))
      (node (ref "U202") (pin "11") (pinfunction "EMIT_11") (pintype "passive"))
    )
    (net (code "46") (name "Net-(R203A-2)") (class "Default")
      (node (ref "R203") (pin "8") (pinfunction "2_8") (pintype "passive"))
      (node (ref "U202") (pin "1") (pinfunction "A_1") (pintype "passive"))
    )
    (net (code "47") (name "Net-(R203B-2)") (class "Default")
      (node (ref "R203") (pin "7") (pinfunction "2_7") (pintype "passive"))
      (node (ref "U202") (pin "3") (pinfunction "A_3") (pintype "passive"))
    )
    (net (code "48") (name "Net-(R203C-2)") (class "Default")
      (node (ref "R203") (pin "6") (pinfunction "2_6") (pintype "passive"))
      (node (ref "U202") (pin "5") (pinfunction "A_5") (pintype "passive"))
    )
    (net (code "49") (name "Net-(R203D-2)") (class "Default")
      (node (ref "R203") (pin "5") (pinfunction "2_5") (pintype "passive"))
      (node (ref "U202") (pin "7") (pinfunction "A_7") (pintype "passive"))
    )
    (net (code "50") (name "Net-(S201B-P$3)") (class "Default")
      (node (ref "S201") (pin "5") (pinfunction "P$3_5") (pintype "bidirectional"))
      (node (ref "U004") (pin "3") (pinfunction "EN_3") (pintype "bidirectional"))
    )
    (net (code "51") (name "Net-(S457B-1)") (class "Default")
      (node (ref "S457") (pin "P$1") (pinfunction "1_P$1") (pintype "bidirectional"))
      (node (ref "S457A") (pin "2") (pinfunction "2_2") (pintype "passive"))
    )
    (net (code "52") (name "Net-(U004-BYP)") (class "Default")
      (node (ref "C001") (pin "1") (pinfunction "1_1") (pintype "passive"))
      (node (ref "U004") (pin "4") (pinfunction "BYP_4") (pintype "bidirectional"))
    )
    (net (code "53") (name "Net-(U201-IN1)") (class "Default")
      (node (ref "U201") (pin "12") (pinfunction "IN4_12") (pintype "bidirectional"))
      (node (ref "U201") (pin "5") (pinfunction "IN1_5") (pintype "bidirectional"))
      (node (ref "U203") (pin "4") (pinfunction "Y_4") (pintype "output"))
    )
    (net (code "54") (name "Net-(U202A-EMIT)") (class "Default")
      (node (ref "Q201") (pin "G") (pinfunction "G_G") (pintype "passive"))
      (node (ref "R201") (pin "1") (pinfunction "1_1") (pintype "passive"))
      (node (ref "U202") (pin "15") (pinfunction "EMIT_15") (pintype "passive"))
    )
    (net (code "55") (name "Net-(U301-PROG)") (class "Default")
      (node (ref "R301") (pin "2") (pinfunction "2_2") (pintype "passive"))
      (node (ref "U301") (pin "5") (pinfunction "PROG_5") (pintype "input"))
    )
    (net (code "56") (name "Net-(U301-STAT)") (class "Default")
      (node (ref "D301") (pin "C") (pinfunction "C_C") (pintype "passive"))
      (node (ref "U301") (pin "1") (pinfunction "STAT_1") (pintype "output"))
    )
    (net (code "57") (name "Net-(U601-CPOUT)") (class "Default")
      (node (ref "C620") (pin "2") (pinfunction "2_2") (pintype "passive"))
      (node (ref "U601") (pin "20") (pinfunction "CPOUT_20") (pintype "bidirectional"))
    )
    (net (code "58") (name "Net-(U601-REGOUT)") (class "Default")
      (node (ref "C610") (pin "1") (pinfunction "1_1") (pintype "passive"))
      (node (ref "U601") (pin "10") (pinfunction "REGOUT_10") (pintype "bidirectional"))
    )
    (net (code "59") (name "VCC") (class "Default")
      (node (ref "C003") (pin "1") (pinfunction "1_1") (pintype "passive"))
      (node (ref "C101") (pin "1") (pinfunction "1_1") (pintype "passive"))
      (node (ref "C423") (pin "1") (pinfunction "1_1") (pintype "passive"))
      (node (ref "C443") (pin "1") (pinfunction "1_1") (pintype "passive"))
      (node (ref "C451") (pin "1") (pinfunction "1_1") (pintype "passive"))
      (node (ref "C463") (pin "1") (pinfunction "1_1") (pintype "passive"))
      (node (ref "C613") (pin "2") (pinfunction "2_2") (pintype "passive"))
      (node (ref "C901") (pin "1") (pinfunction "1_1") (pintype "passive"))
      (node (ref "C906") (pin "1") (pinfunction "1_1") (pintype "passive"))
      (node (ref "D001") (pin "2") (pinfunction "A_2") (pintype "passive"))
      (node (ref "D001") (pin "4") (pinfunction "A_4") (pintype "passive"))
      (node (ref "D001") (pin "6") (pinfunction "A_6") (pintype "passive"))
      (node (ref "J401") (pin "8") (pinfunction "8_8") (pintype "passive"))
      (node (ref "J701") (pin "4") (pinfunction "VCC_4") (pintype "bidirectional"))
      (node (ref "Q050") (pin "2") (pinfunction "S_2") (pintype "passive"))
      (node (ref "R015") (pin "1") (pinfunction "1_1") (pintype "passive"))
      (node (ref "R401") (pin "5") (pinfunction "2_5") (pintype "passive"))
      (node (ref "R401") (pin "6") (pinfunction "2_6") (pintype "passive"))
      (node (ref "R401") (pin "7") (pinfunction "2_7") (pintype "passive"))
      (node (ref "R401") (pin "8") (pinfunction "2_8") (pintype "passive"))
      (node (ref "U003") (pin "23") (pinfunction "VDD3-1_23") (pintype "power_in"))
      (node (ref "U003") (pin "43") (pinfunction "VDD3-2_43") (pintype "power_in"))
      (node (ref "U003") (pin "51") (pinfunction "VDD3-3_51") (pintype "power_in"))
      (node (ref "U003") (pin "63") (pinfunction "VREF_63") (pintype "input"))
      (node (ref "U003") (pin "7") (pinfunction "VDDA3_7") (pintype "power_in"))
      (node (ref "U004") (pin "5") (pinfunction "VOUT_5") (pintype "bidirectional"))
      (node (ref "U101") (pin "2") (pinfunction "VDD_2") (pintype "power_in"))
      (node (ref "U101") (pin "3") (pinfunction "VDDIO_3") (pintype "power_in"))
      (node (ref "U601") (pin "13") (pinfunction "VDD_13") (pintype "bidirectional"))
      (node (ref "U601") (pin "3") (pinfunction "VDD_3") (pintype "bidirectional"))
      (node (ref "U601") (pin "8") (pinfunction "VLOGIC_8") (pintype "bidirectional"))
      (node (ref "U902") (pin "1") (pinfunction "VDDIO_1") (pintype "power_in"))
      (node (ref "U902") (pin "6") (pinfunction "VS_6") (pintype "power_in"))
      (node (ref "U902") (pin "7") (pinfunction "CS_7") (pintype "input"))
    )
    (net (code "60") (name "unconnected-(J701-CD-PadCD1)") (class "Default")
      (node (ref "J701") (pin "CD1") (pinfunction "CD_CD1") (pintype "bidirectional"))
    )
    (net (code "61") (name "unconnected-(J701-NC-Pad1)") (class "Default")
      (node (ref "J701") (pin "1") (pinfunction "NC_1") (pintype "bidirectional"))
    )
    (net (code "62") (name "unconnected-(J701-RSV-Pad8)") (class "Default")
      (node (ref "J701") (pin "8") (pinfunction "RSV_8") (pintype "bidirectional"))
    )
    (net (code "63") (name "unconnected-(U003-(AD0.1{slash}CAP0.2{slash}MAT0.2)P0.28-Pad13)") (class "Default")
      (node (ref "U003") (pin "13") (pinfunction "(AD0.1/CAP0.2/MAT0.2)P0.28_13") (pintype "bidirectional"))
    )
    (net (code "64") (name "unconnected-(U003-(AD0.2{slash}CAP0.3{slash}MAT0.3)P0.29-Pad14)") (class "Default")
      (node (ref "U003") (pin "14") (pinfunction "(AD0.2/CAP0.3/MAT0.3)P0.29_14") (pintype "bidirectional"))
    )
    (net (code "65") (name "unconnected-(U003-(AD0.4{slash}AOUT)P0.25-Pad9)") (class "Default")
      (node (ref "U003") (pin "9") (pinfunction "(AD0.4/AOUT)P0.25_9") (pintype "bidirectional"))
    )
    (net (code "66") (name "unconnected-(U003-(AD1.7{slash}CAP0.0{slash}MAT0.0)P0.22-Pad2)") (class "Default")
      (node (ref "U003") (pin "2") (pinfunction "(AD1.7/CAP0.0/MAT0.0)P0.22_2") (pintype "bidirectional"))
    )
    (net (code "67") (name "unconnected-(U003-(CAP1.3{slash}MISO1{slash}MAT1.3)P0.18-Pad53)") (class "Default")
      (node (ref "U003") (pin "53") (pinfunction "(CAP1.3/MISO1/MAT1.3)P0.18_53") (pintype "bidirectional"))
    )
    (net (code "68") (name "unconnected-(U003-(CTS1{slash}CAP1.1{slash}SCL1)P0.11-Pad37)") (class "Default")
      (node (ref "U003") (pin "37") (pinfunction "(CTS1/CAP1.1/SCL1)P0.11_37") (pintype "bidirectional"))
    )
    (net (code "69") (name "unconnected-(U003-(DSR1{slash}MAT1.0{slash}AD1.3)P0.12-Pad38)") (class "Default")
      (node (ref "U003") (pin "38") (pinfunction "(DSR1/MAT1.0/AD1.3)P0.12_38") (pintype "bidirectional"))
    )
    (net (code "70") (name "unconnected-(U003-(DTR1{slash}MAT1.1{slash}AD1.4)P0.13-Pad39)") (class "Default")
      (node (ref "U003") (pin "39") (pinfunction "(DTR1/MAT1.1/AD1.4)P0.13_39") (pintype "bidirectional"))
    )
    (net (code "71") (name "unconnected-(U003-(EINT0{slash}MAT0.2{slash}CAP0.2)P0.16-Pad46)") (class "Default")
      (node (ref "U003") (pin "46") (pinfunction "(EINT0/MAT0.2/CAP0.2)P0.16_46") (pintype "bidirectional"))
    )
    (net (code "72") (name "unconnected-(U003-(MAT1.2{slash}MOSI1{slash}CAP1.2)P0.19-Pad54)") (class "Default")
      (node (ref "U003") (pin "54") (pinfunction "(MAT1.2/MOSI1/CAP1.2)P0.19_54") (pintype "bidirectional"))
    )
    (net (code "73") (name "unconnected-(U003-(MAT1.3{slash}SSEL1{slash}EINT3)P0.20-Pad55)") (class "Default")
      (node (ref "U003") (pin "55") (pinfunction "(MAT1.3/SSEL1/EINT3)P0.20_55") (pintype "bidirectional"))
    )
    (net (code "74") (name "unconnected-(U003-(PWM5{slash}AD1.6{slash}CAP1.3)P0.21-Pad1)") (class "Default")
      (node (ref "U003") (pin "1") (pinfunction "(PWM5/AD1.6/CAP1.3)P0.21_1") (pintype "bidirectional"))
    )
    (net (code "75") (name "unconnected-(U003-P1.16(TRACEPKT0)-Pad16)") (class "Default")
      (node (ref "U003") (pin "16") (pinfunction "P1.16(TRACEPKT0)_16") (pintype "bidirectional"))
    )
    (net (code "76") (name "unconnected-(U003-P1.17(TRACEPKT1)-Pad12)") (class "Default")
      (node (ref "U003") (pin "12") (pinfunction "P1.17(TRACEPKT1)_12") (pintype "bidirectional"))
    )
    (net (code "77") (name "unconnected-(U003-P1.18(TRACEPKT2)-Pad8)") (class "Default")
      (node (ref "U003") (pin "8") (pinfunction "P1.18(TRACEPKT2)_8") (pintype "bidirectional"))
    )
    (net (code "78") (name "unconnected-(U003-P1.19(TRACEPKT3)-Pad4)") (class "Default")
      (node (ref "U003") (pin "4") (pinfunction "P1.19(TRACEPKT3)_4") (pintype "bidirectional"))
    )
    (net (code "79") (name "unconnected-(U003-P1.20(TRACESYNC)-Pad48)") (class "Default")
      (node (ref "U003") (pin "48") (pinfunction "P1.20(TRACESYNC)_48") (pintype "bidirectional"))
    )
    (net (code "80") (name "unconnected-(U003-P1.21(PIPESTAT0)-Pad44)") (class "Default")
      (node (ref "U003") (pin "44") (pinfunction "P1.21(PIPESTAT0)_44") (pintype "bidirectional"))
    )
    (net (code "81") (name "unconnected-(U003-P1.22(PIPESTAT1)-Pad40)") (class "Default")
      (node (ref "U003") (pin "40") (pinfunction "P1.22(PIPESTAT1)_40") (pintype "bidirectional"))
    )
    (net (code "82") (name "unconnected-(U003-P1.23(PIPESTAT2)-Pad36)") (class "Default")
      (node (ref "U003") (pin "36") (pinfunction "P1.23(PIPESTAT2)_36") (pintype "bidirectional"))
    )
    (net (code "83") (name "unconnected-(U003-P1.24(TRACECLK)-Pad32)") (class "Default")
      (node (ref "U003") (pin "32") (pinfunction "P1.24(TRACECLK)_32") (pintype "bidirectional"))
    )
    (net (code "84") (name "unconnected-(U003-P1.25(EXTIN0)-Pad28)") (class "Default")
      (node (ref "U003") (pin "28") (pinfunction "P1.25(EXTIN0)_28") (pintype "bidirectional"))
    )
    (net (code "85") (name "unconnected-(U003-P1.26(RTCK)-Pad24)") (class "Default")
      (node (ref "U003") (pin "24") (pinfunction "P1.26(RTCK)_24") (pintype "bidirectional"))
    )
    (net (code "86") (name "unconnected-(U003-P1.27(TDO)-Pad64)") (class "Default")
      (node (ref "U003") (pin "64") (pinfunction "P1.27(TDO)_64") (pintype "bidirectional"))
    )
    (net (code "87") (name "unconnected-(U003-P1.28(TDI)-Pad60)") (class "Default")
      (node (ref "U003") (pin "60") (pinfunction "P1.28(TDI)_60") (pintype "bidirectional"))
    )
    (net (code "88") (name "unconnected-(U003-P1.29(TCK)-Pad56)") (class "Default")
      (node (ref "U003") (pin "56") (pinfunction "P1.29(TCK)_56") (pintype "bidirectional"))
    )
    (net (code "89") (name "unconnected-(U003-P1.30(TMS)-Pad52)") (class "Default")
      (node (ref "U003") (pin "52") (pinfunction "P1.30(TMS)_52") (pintype "bidirectional"))
    )
    (net (code "90") (name "unconnected-(U003-P1.31({slash}TRST)-Pad20)") (class "Default")
      (node (ref "U003") (pin "20") (pinfunction "P1.31(/TRST)_20") (pintype "bidirectional"))
    )
    (net (code "91") (name "unconnected-(U003-RTXC2-Pad5)") (class "Default")
      (node (ref "U003") (pin "5") (pinfunction "RTXC2_5") (pintype "output"))
    )
    (net (code "92") (name "unconnected-(U601-CLKOUT-Pad22)") (class "Default")
      (node (ref "U601") (pin "22") (pinfunction "CLKOUT_22") (pintype "bidirectional"))
    )
    (net (code "93") (name "unconnected-(U601-ES_CL-Pad7)") (class "Default")
      (node (ref "U601") (pin "7") (pinfunction "ES_CL_7") (pintype "bidirectional"))
    )
    (net (code "94") (name "unconnected-(U601-ES_DA-Pad6)") (class "Default")
      (node (ref "U601") (pin "6") (pinfunction "ES_DA_6") (pintype "bidirectional"))
    )
    (net (code "95") (name "unconnected-(U902-INT1-Pad8)") (class "Default")
      (node (ref "U902") (pin "8") (pinfunction "INT1_8") (pintype "output"))
    )
    (net (code "96") (name "unconnected-(U902-INT2-Pad9)") (class "Default")
      (node (ref "U902") (pin "9") (pinfunction "INT2_9") (pintype "output"))
    )
  )
)
